# controller.net
KiCad netlist of a schematic drawn in EAGLE
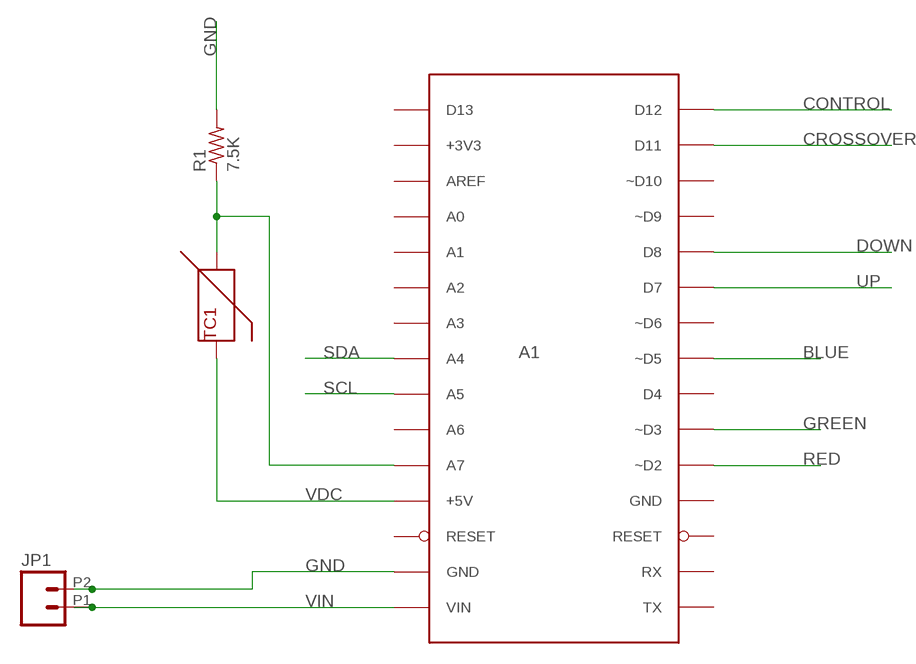
[diagram p0: schematic, sheet 1]
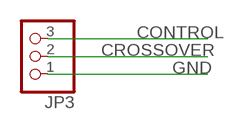
[diagram p1: schematic, sheet 2]
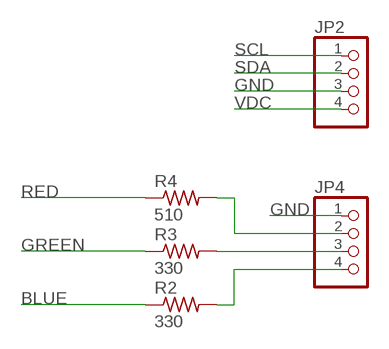
[diagram p2: schematic, sheet 3]
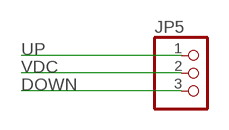
[diagram p3: schematic, sheet 4]

(export (version "E")
  (design (tool "Eeschema 10.0.6"))
  (components
    (comp (ref "JP5")
      (value "PINHD-1X3")
      (footprint "eagle-import:1X03")
      (libsource (lib "eagle-import") (part "PINHD-1X3"))
    )
    (comp (ref "A1")
      (value "NANO_EVERY")
      (footprint "eagle-import:NANO_EVERY_SOCKET")
      (libsource (lib "eagle-import") (part "NANO_EVERY"))
    )
    (comp (ref "JP1")
      (value "1716060000")
      (footprint "eagle-import:WM2-2")
      (libsource (lib "eagle-import") (part "1716060000"))
    )
    (comp (ref "R1")
      (value "7.5K")
      (footprint "eagle-import:CFR-25")
      (libsource (lib "eagle-import") (part "YAGEO_CFR"))
    )
    (comp (ref "TC1")
      (value "MA100GG103AN")
      (footprint "eagle-import:MA100GG103AN")
      (libsource (lib "eagle-import") (part "MA100GG103AN"))
    )
    (comp (ref "JP2")
      (value "PINHD-1X4")
      (footprint "eagle-import:1X04")
      (libsource (lib "eagle-import") (part "PINHD-1X4"))
    )
    (comp (ref "JP4")
      (value "PINHD-1X4")
      (footprint "eagle-import:1X04")
      (libsource (lib "eagle-import") (part "PINHD-1X4"))
    )
    (comp (ref "R2")
      (value "330")
      (footprint "eagle-import:CFR-25")
      (libsource (lib "eagle-import") (part "YAGEO-CFR-25"))
    )
    (comp (ref "R3")
      (value "330")
      (footprint "eagle-import:CFR-25")
      (libsource (lib "eagle-import") (part "YAGEO-CFR-25"))
    )
    (comp (ref "R4")
      (value "510")
      (footprint "eagle-import:CFR-25")
      (libsource (lib "eagle-import") (part "YAGEO-CFR-25"))
    )
    (comp (ref "JP3")
      (value "PINHD-1X3/90")
      (footprint "eagle-import:1X03_90")
      (libsource (lib "eagle-import") (part "PINHD-1X3/90"))
    )
  )
  (nets
    (net (code "1") (name "BLUE") (class "Default")
      (node (ref "A1") (pin "~D5") (pinfunction "~{D5}_~D5") (pintype "bidirectional"))
      (node (ref "R2") (pin "P$1") (pinfunction "1_P$1") (pintype "passive"))
    )
    (net (code "2") (name "CONTROL") (class "Default")
      (node (ref "A1") (pin "D12") (pinfunction "D12_D12") (pintype "bidirectional"))
      (node (ref "JP3") (pin "3") (pinfunction "3_3") (pintype "passive"))
    )
    (net (code "3") (name "CROSSOVER") (class "Default")
      (node (ref "A1") (pin "D11") (pinfunction "D11_D11") (pintype "bidirectional"))
      (node (ref "JP3") (pin "2") (pinfunction "2_2") (pintype "passive"))
    )
    (net (code "4") (name "DOWN") (class "Default")
      (node (ref "A1") (pin "D8") (pinfunction "D8_D8") (pintype "bidirectional"))
      (node (ref "JP5") (pin "3") (pinfunction "3_3") (pintype "passive"))
    )
    (net (code "5") (name "GND") (class "Default")
      (node (ref "A1") (pin "GND@1") (pinfunction "GND_GND@1") (pintype "bidirectional"))
      (node (ref "JP1") (pin "P2") (pinfunction "2_P2") (pintype "passive"))
      (node (ref "JP2") (pin "3") (pinfunction "3_3") (pintype "passive"))
      (node (ref "JP3") (pin "1") (pinfunction "1_1") (pintype "passive"))
      (node (ref "JP4") (pin "1") (pinfunction "1_1") (pintype "passive"))
      (node (ref "R1") (pin "P$2") (pinfunction "2_P$2") (pintype "passive"))
    )
    (net (code "6") (name "GREEN") (class "Default")
      (node (ref "A1") (pin "~D3") (pinfunction "~{D3}_~D3") (pintype "bidirectional"))
      (node (ref "R3") (pin "P$1") (pinfunction "1_P$1") (pintype "passive"))
    )
    (net (code "7") (name "Net-(R1-1)") (class "Default")
      (node (ref "A1") (pin "A7") (pinfunction "A7_A7") (pintype "bidirectional"))
      (node (ref "R1") (pin "P$1") (pinfunction "1_P$1") (pintype "passive"))
      (node (ref "TC1") (pin "P$2") (pinfunction "P$2_P$2") (pintype "passive"))
    )
    (net (code "8") (name "Net-(R2-2)") (class "Default")
      (node (ref "JP4") (pin "4") (pinfunction "4_4") (pintype "passive"))
      (node (ref "R2") (pin "P$2") (pinfunction "2_P$2") (pintype "passive"))
    )
    (net (code "9") (name "Net-(R3-2)") (class "Default")
      (node (ref "JP4") (pin "3") (pinfunction "3_3") (pintype "passive"))
      (node (ref "R3") (pin "P$2") (pinfunction "2_P$2") (pintype "passive"))
    )
    (net (code "10") (name "Net-(R4-2)") (class "Default")
      (node (ref "JP4") (pin "2") (pinfunction "2_2") (pintype "passive"))
      (node (ref "R4") (pin "P$2") (pinfunction "2_P$2") (pintype "passive"))
    )
    (net (code "11") (name "RED") (class "Default")
      (node (ref "A1") (pin "~D2") (pinfunction "~{D2}_~D2") (pintype "bidirectional"))
      (node (ref "R4") (pin "P$1") (pinfunction "1_P$1") (pintype "passive"))
    )
    (net (code "12") (name "SCL") (class "Default")
      (node (ref "A1") (pin "A5") (pinfunction "A5_A5") (pintype "bidirectional"))
      (node (ref "JP2") (pin "1") (pinfunction "1_1") (pintype "passive"))
    )
    (net (code "13") (name "SDA") (class "Default")
      (node (ref "A1") (pin "A4") (pinfunction "A4_A4") (pintype "bidirectional"))
      (node (ref "JP2") (pin "2") (pinfunction "2_2") (pintype "passive"))
    )
    (net (code "14") (name "UP") (class "Default")
      (node (ref "A1") (pin "D7") (pinfunction "D7_D7") (pintype "bidirectional"))
      (node (ref "JP5") (pin "1") (pinfunction "1_1") (pintype "passive"))
    )
    (net (code "15") (name "VDC") (class "Default")
      (node (ref "A1") (pin "+5V") (pinfunction "+5V_+5V") (pintype "output"))
      (node (ref "JP2") (pin "4") (pinfunction "4_4") (pintype "passive"))
      (node (ref "JP5") (pin "2") (pinfunction "2_2") (pintype "passive"))
      (node (ref "TC1") (pin "P$1") (pinfunction "P$1_P$1") (pintype "passive"))
    )
    (net (code "16") (name "VIN") (class "Default")
      (node (ref "A1") (pin "VIN") (pinfunction "VIN_VIN") (pintype "power_in"))
      (node (ref "JP1") (pin "P1") (pinfunction "1_P1") (pintype "passive"))
    )
    (net (code "17") (name "unconnected-(A1-GND-PadGND@2)") (class "Default")
      (node (ref "A1") (pin "GND@2") (pinfunction "GND_GND@2") (pintype "bidirectional"))
    )
    (net (code "18") (name "unconnected-(A1-Pad+3V3)") (class "Default")
      (node (ref "A1") (pin "+3V3") (pinfunction "+3V3_+3V3") (pintype "output"))
    )
    (net (code "19") (name "unconnected-(A1-PadA0)") (class "Default")
      (node (ref "A1") (pin "A0") (pinfunction "A0_A0") (pintype "bidirectional"))
    )
    (net (code "20") (name "unconnected-(A1-PadA1)") (class "Default")
      (node (ref "A1") (pin "A1") (pinfunction "A1_A1") (pintype "bidirectional"))
    )
    (net (code "21") (name "unconnected-(A1-PadA2)") (class "Default")
      (node (ref "A1") (pin "A2") (pinfunction "A2_A2") (pintype "bidirectional"))
    )
    (net (code "22") (name "unconnected-(A1-PadA3)") (class "Default")
      (node (ref "A1") (pin "A3") (pinfunction "A3_A3") (pintype "bidirectional"))
    )
    (net (code "23") (name "unconnected-(A1-PadA6)") (class "Default")
      (node (ref "A1") (pin "A6") (pinfunction "A6_A6") (pintype "bidirectional"))
    )
    (net (code "24") (name "unconnected-(A1-PadAREF)") (class "Default")
      (node (ref "A1") (pin "AREF") (pinfunction "AREF_AREF") (pintype "bidirectional"))
    )
    (net (code "25") (name "unconnected-(A1-PadD4)") (class "Default")
      (node (ref "A1") (pin "D4") (pinfunction "D4_D4") (pintype "bidirectional"))
    )
    (net (code "26") (name "unconnected-(A1-PadD13)") (class "Default")
      (node (ref "A1") (pin "D13") (pinfunction "D13_D13") (pintype "bidirectional"))
    )
    (net (code "27") (name "unconnected-(A1-PadRX)") (class "Default")
      (node (ref "A1") (pin "RX") (pinfunction "RX_RX") (pintype "bidirectional"))
    )
    (net (code "28") (name "unconnected-(A1-PadTX)") (class "Default")
      (node (ref "A1") (pin "TX") (pinfunction "TX_TX") (pintype "bidirectional"))
    )
    (net (code "29") (name "unconnected-(A1-RESET-PadRESET@1)") (class "Default")
      (node (ref "A1") (pin "RESET@1") (pinfunction "RESET_RESET@1") (pintype "input"))
    )
    (net (code "30") (name "unconnected-(A1-RESET-PadRESET@2)") (class "Default")
      (node (ref "A1") (pin "RESET@2") (pinfunction "RESET_RESET@2") (pintype "input"))
    )
    (net (code "31") (name "unconnected-(A1-~{D6}-Pad~D6)") (class "Default")
      (node (ref "A1") (pin "~D6") (pinfunction "~{D6}_~D6") (pintype "bidirectional"))
    )
    (net (code "32") (name "unconnected-(A1-~{D9}-Pad~D9)") (class "Default")
      (node (ref "A1") (pin "~D9") (pinfunction "~{D9}_~D9") (pintype "bidirectional"))
    )
    (net (code "33") (name "unconnected-(A1-~{D10}-Pad~D10)") (class "Default")
      (node (ref "A1") (pin "~D10") (pinfunction "~{D10}_~D10") (pintype "bidirectional"))
    )
  )
)
